# Sheet4_LCD_Interface.net
KiCad netlist of a schematic drawn in Altium Designer
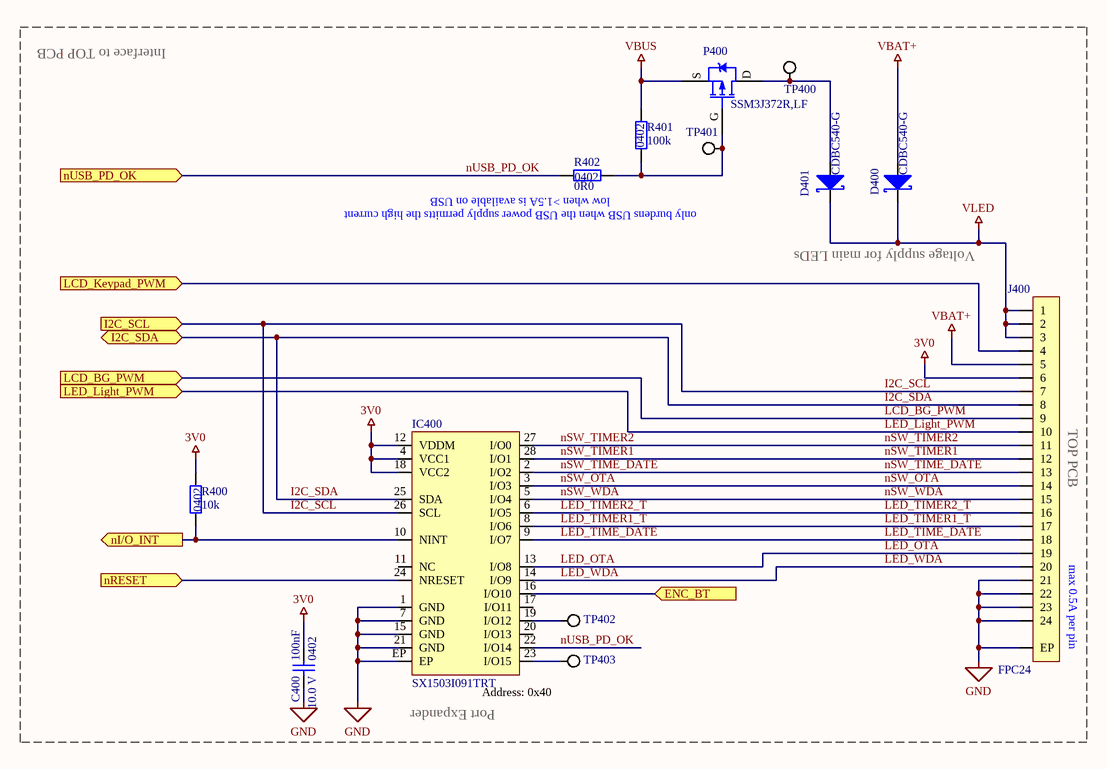
[diagram p0: Sheet4_LCD_Interface.SchDoc]

(export (version "E")
  (design (tool "Eeschema 10.0.6"))
  (components
    (comp (ref "C400")
      (value "C 100nF 0402 10V")
      (footprint "0402")
      (description "CAP CER 0.1UF 10V X5R 0402")
      (fields
        (field (name "MANUFACTURER") "Samsung Electro-Mechanics")
        (field (name "MANUFACTURER PART NUMBER") "CL05A104MP5NNNC")
        (field (name "CAPACITANCE") "100nF")
        (field (name "VOLTAGE") "10.0 V")
      )
      (libsource (lib "CS_Part_Library") (part "CAP_100nF_10V_0402"))
    )
    (comp (ref "D400")
      (value "D SCH 40V 5A")
      (footprint "DO-214AB")
      (description "DIODE SCHOTTKY 40V 5A DO214AB")
      (fields
        (field (name "MANUFACTURER") "Comchip Technology")
        (field (name "MANUFACTURER PART NUMBER") "CDBC540-G")
      )
      (libsource (lib "CS_Part_Library") (part "D_SCH_40V_5A"))
    )
    (comp (ref "D401")
      (value "D SCH 40V 5A")
      (footprint "DO-214AB")
      (description "DIODE SCHOTTKY 40V 5A DO214AB")
      (fields
        (field (name "MANUFACTURER") "Comchip Technology")
        (field (name "MANUFACTURER PART NUMBER") "CDBC540-G")
      )
      (libsource (lib "CS_Part_Library") (part "D_SCH_40V_5A"))
    )
    (comp (ref "IC400")
      (value "SX1503I091TRT")
      (footprint "UFQFN-28-EP")
      (description "IC GPIO EXPANDER I2C 16CH 28-QFN")
      (fields (field (name "MANUFACTURER") "Semtech Corporation"))
      (libsource (lib "CS_Part_Library") (part "IC_16ch_Port_Extender_2"))
    )
    (comp (ref "J400")
      (value "FPC24")
      (footprint "J_FPC_522712479")
      (description "CONN FPC BOT 24 PIN 1mm Pitch")
      (fields (field (name "MANUFACTURER") "MOLEX") (field (name "MANUFACTURER PART NUMBER") "522712479"))
      (libsource (lib "Symbols") (part "J_FPC24_DS"))
    )
    (comp (ref "P400")
      (value "P PMOS 30V 6A")
      (footprint "SOT-23-3-F")
      (description "MOSFET P-CH 30V 6A SOT23F")
      (fields
        (field (name "MANUFACTURER") "Toshiba Semiconductor and Storage")
        (field (name "MANUFACTURER PART NUMBER") "SSM3J372R,LF")
      )
      (libsource (lib "Symbols") (part "P_PCH_30V_1W"))
    )
    (comp (ref "R400")
      (value "R 10k 0402")
      (footprint "0402")
      (description "RES 10K OHM 1% 1/16W 0402")
      (fields
        (field (name "MANUFACTURER") "YAGEO")
        (field (name "MANUFACTURER PART NUMBER") "RC0402FR-0710KL")
        (field (name "RESISTANCE") "10k")
      )
      (libsource (lib "CS_Part_Library") (part "R_10k_0402"))
    )
    (comp (ref "R401")
      (value "R 1k8 0402")
      (footprint "0402")
      (description "RES 100K OHM 5% 1/16W 0402")
      (fields
        (field (name "MANUFACTURER") "YAGEO")
        (field (name "MANUFACTURER PART NUMBER") "RC0402JR-07100KL")
        (field (name "RESISTANCE") "100k")
      )
      (libsource (lib "CS_Part_Library") (part "R_100k_0402"))
    )
    (comp (ref "R402")
      (value "R 0R0 0402")
      (footprint "0402")
      (description "RES 0 OHM JUMPER 1/16W 0402")
      (fields
        (field (name "MANUFACTURER") "Stackpole Electronics Inc")
        (field (name "MANUFACTURER PART NUMBER") "RMCF0402ZT0R00")
        (field (name "RESISTANCE") "0R0")
      )
      (libsource (lib "CS_Part_Library") (part "R_0R0_0402"))
    )
    (comp (ref "TP400")
      (value "TP")
      (footprint "TP_1mm")
      (description "Test Point 1mm")
      (libsource (lib "Symbols") (part "TP_1mm"))
    )
    (comp (ref "TP401")
      (value "TP")
      (footprint "TP_1mm")
      (description "Test Point 1mm")
      (libsource (lib "Symbols") (part "TP_1mm"))
    )
    (comp (ref "TP402")
      (value "TP")
      (footprint "TP_1mm")
      (description "Test Point 1mm")
      (libsource (lib "Symbols") (part "TP_1mm"))
    )
    (comp (ref "TP403")
      (value "TP")
      (footprint "TP_1mm")
      (description "Test Point 1mm")
      (libsource (lib "Symbols") (part "TP_1mm"))
    )
  )
  (nets
    (net (code "1") (name "/ENC_BT") (class "Default")
      (node (ref "IC400") (pin "16") (pinfunction "I/O10_16") (pintype "passive"))
    )
    (net (code "2") (name "/I2C_SCL") (class "Default")
      (node (ref "IC400") (pin "26") (pinfunction "SCL_26") (pintype "passive"))
      (node (ref "J400") (pin "7") (pinfunction "7_7") (pintype "passive"))
    )
    (net (code "3") (name "/I2C_SDA") (class "Default")
      (node (ref "IC400") (pin "25") (pinfunction "SDA_25") (pintype "passive"))
      (node (ref "J400") (pin "8") (pinfunction "8_8") (pintype "passive"))
    )
    (net (code "4") (name "/LCD_BG_PWM") (class "Default")
      (node (ref "J400") (pin "9") (pinfunction "9_9") (pintype "passive"))
    )
    (net (code "5") (name "/LCD_Keypad_PWM") (class "Default")
      (node (ref "J400") (pin "4") (pinfunction "4_4") (pintype "passive"))
    )
    (net (code "6") (name "/LED_Light_PWM") (class "Default")
      (node (ref "J400") (pin "10") (pinfunction "10_10") (pintype "passive"))
    )
    (net (code "7") (name "/LED_OTA") (class "Default")
      (node (ref "IC400") (pin "13") (pinfunction "I/O8_13") (pintype "passive"))
      (node (ref "J400") (pin "19") (pinfunction "19_19") (pintype "passive"))
    )
    (net (code "8") (name "/LED_TIMER1_T") (class "Default")
      (node (ref "IC400") (pin "8") (pinfunction "I/O6_8") (pintype "passive"))
      (node (ref "J400") (pin "17") (pinfunction "17_17") (pintype "passive"))
    )
    (net (code "9") (name "/LED_TIMER2_T") (class "Default")
      (node (ref "IC400") (pin "6") (pinfunction "I/O5_6") (pintype "passive"))
      (node (ref "J400") (pin "16") (pinfunction "16_16") (pintype "passive"))
    )
    (net (code "10") (name "/LED_TIME_DATE") (class "Default")
      (node (ref "IC400") (pin "9") (pinfunction "I/O7_9") (pintype "passive"))
      (node (ref "J400") (pin "18") (pinfunction "18_18") (pintype "passive"))
    )
    (net (code "11") (name "/LED_WDA") (class "Default")
      (node (ref "IC400") (pin "14") (pinfunction "I/O9_14") (pintype "passive"))
      (node (ref "J400") (pin "20") (pinfunction "20_20") (pintype "passive"))
    )
    (net (code "12") (name "/nI{slash}O_INT") (class "Default")
      (node (ref "IC400") (pin "10") (pinfunction "NINT_10") (pintype "passive"))
      (node (ref "R400") (pin "1") (pinfunction "1_1") (pintype "passive"))
    )
    (net (code "13") (name "/nRESET") (class "Default")
      (node (ref "IC400") (pin "24") (pinfunction "NRESET_24") (pintype "passive"))
    )
    (net (code "14") (name "/nSW_OTA") (class "Default")
      (node (ref "IC400") (pin "3") (pinfunction "I/O3_3") (pintype "passive"))
      (node (ref "J400") (pin "14") (pinfunction "14_14") (pintype "passive"))
    )
    (net (code "15") (name "/nSW_TIMER1") (class "Default")
      (node (ref "IC400") (pin "28") (pinfunction "I/O1_28") (pintype "passive"))
      (node (ref "J400") (pin "12") (pinfunction "12_12") (pintype "passive"))
    )
    (net (code "16") (name "/nSW_TIMER2") (class "Default")
      (node (ref "IC400") (pin "27") (pinfunction "I/O0_27") (pintype "passive"))
      (node (ref "J400") (pin "11") (pinfunction "11_11") (pintype "passive"))
    )
    (net (code "17") (name "/nSW_TIME_DATE") (class "Default")
      (node (ref "IC400") (pin "2") (pinfunction "I/O2_2") (pintype "passive"))
      (node (ref "J400") (pin "13") (pinfunction "13_13") (pintype "passive"))
    )
    (net (code "18") (name "/nSW_WDA") (class "Default")
      (node (ref "IC400") (pin "5") (pinfunction "I/O4_5") (pintype "passive"))
      (node (ref "J400") (pin "15") (pinfunction "15_15") (pintype "passive"))
    )
    (net (code "19") (name "/nUSB_PD_OK") (class "Default")
      (node (ref "IC400") (pin "22") (pinfunction "I/O14_22") (pintype "passive"))
      (node (ref "R402") (pin "2") (pinfunction "2_2") (pintype "passive"))
    )
    (net (code "20") (name "3V0") (class "Default")
      (node (ref "C400") (pin "2") (pinfunction "2_2") (pintype "passive"))
      (node (ref "IC400") (pin "12") (pinfunction "VDDM_12") (pintype "passive"))
      (node (ref "IC400") (pin "18") (pinfunction "VCC2_18") (pintype "passive"))
      (node (ref "IC400") (pin "4") (pinfunction "VCC1_4") (pintype "passive"))
      (node (ref "J400") (pin "6") (pinfunction "6_6") (pintype "passive"))
      (node (ref "R400") (pin "2") (pinfunction "2_2") (pintype "passive"))
    )
    (net (code "21") (name "GND") (class "Default")
      (node (ref "C400") (pin "1") (pinfunction "1_1") (pintype "passive"))
      (node (ref "IC400") (pin "1") (pinfunction "GND_1") (pintype "passive"))
      (node (ref "IC400") (pin "15") (pinfunction "GND_15") (pintype "passive"))
      (node (ref "IC400") (pin "21") (pinfunction "GND_21") (pintype "passive"))
      (node (ref "IC400") (pin "7") (pinfunction "GND_7") (pintype "passive"))
      (node (ref "IC400") (pin "EP") (pinfunction "EP_EP") (pintype "passive"))
      (node (ref "J400") (pin "21") (pinfunction "21_21") (pintype "passive"))
      (node (ref "J400") (pin "22") (pinfunction "22_22") (pintype "passive"))
      (node (ref "J400") (pin "23") (pinfunction "23_23") (pintype "passive"))
      (node (ref "J400") (pin "24") (pinfunction "24_24") (pintype "passive"))
      (node (ref "J400") (pin "EP") (pinfunction "EP_EP") (pintype "passive"))
    )
    (net (code "22") (name "Net-(D401-A)") (class "Default")
      (node (ref "D401") (pin "2") (pinfunction "A_2") (pintype "passive"))
      (node (ref "P400") (pin "3") (pinfunction "D_3") (pintype "passive"))
      (node (ref "TP400") (pin "1") (pinfunction "TP_1") (pintype "passive"))
    )
    (net (code "23") (name "Net-(IC400-I{slash}O12)") (class "Default")
      (node (ref "IC400") (pin "19") (pinfunction "I/O12_19") (pintype "passive"))
      (node (ref "TP402") (pin "1") (pinfunction "TP_1") (pintype "passive"))
    )
    (net (code "24") (name "Net-(IC400-I{slash}O15)") (class "Default")
      (node (ref "IC400") (pin "23") (pinfunction "I/O15_23") (pintype "passive"))
      (node (ref "TP403") (pin "1") (pinfunction "TP_1") (pintype "passive"))
    )
    (net (code "25") (name "Net-(P400-G)") (class "Default")
      (node (ref "P400") (pin "1") (pinfunction "G_1") (pintype "passive"))
      (node (ref "R401") (pin "1") (pinfunction "1_1") (pintype "passive"))
      (node (ref "R402") (pin "1") (pinfunction "1_1") (pintype "passive"))
      (node (ref "TP401") (pin "1") (pinfunction "TP_1") (pintype "passive"))
    )
    (net (code "26") (name "VBAT+") (class "Default")
      (node (ref "D400") (pin "2") (pinfunction "A_2") (pintype "passive"))
      (node (ref "J400") (pin "5") (pinfunction "5_5") (pintype "passive"))
    )
    (net (code "27") (name "VBUS") (class "Default")
      (node (ref "P400") (pin "2") (pinfunction "S_2") (pintype "passive"))
      (node (ref "R401") (pin "2") (pinfunction "2_2") (pintype "passive"))
    )
    (net (code "28") (name "VLED") (class "Default")
      (node (ref "D400") (pin "1") (pinfunction "K_1") (pintype "passive"))
      (node (ref "D401") (pin "1") (pinfunction "K_1") (pintype "passive"))
      (node (ref "J400") (pin "1") (pinfunction "1_1") (pintype "passive"))
      (node (ref "J400") (pin "2") (pinfunction "2_2") (pintype "passive"))
      (node (ref "J400") (pin "3") (pinfunction "3_3") (pintype "passive"))
    )
    (net (code "29") (name "unconnected-(IC400-I{slash}O11-Pad17)") (class "Default")
      (node (ref "IC400") (pin "17") (pinfunction "I/O11_17") (pintype "passive"))
    )
    (net (code "30") (name "unconnected-(IC400-I{slash}O13-Pad20)") (class "Default")
      (node (ref "IC400") (pin "20") (pinfunction "I/O13_20") (pintype "passive"))
    )
    (net (code "31") (name "unconnected-(IC400-NC-Pad11)") (class "Default")
      (node (ref "IC400") (pin "11") (pinfunction "NC_11") (pintype "passive"))
    )
  )
)
